# TopLevel.net
KiCad netlist of a schematic drawn in Altium Designer
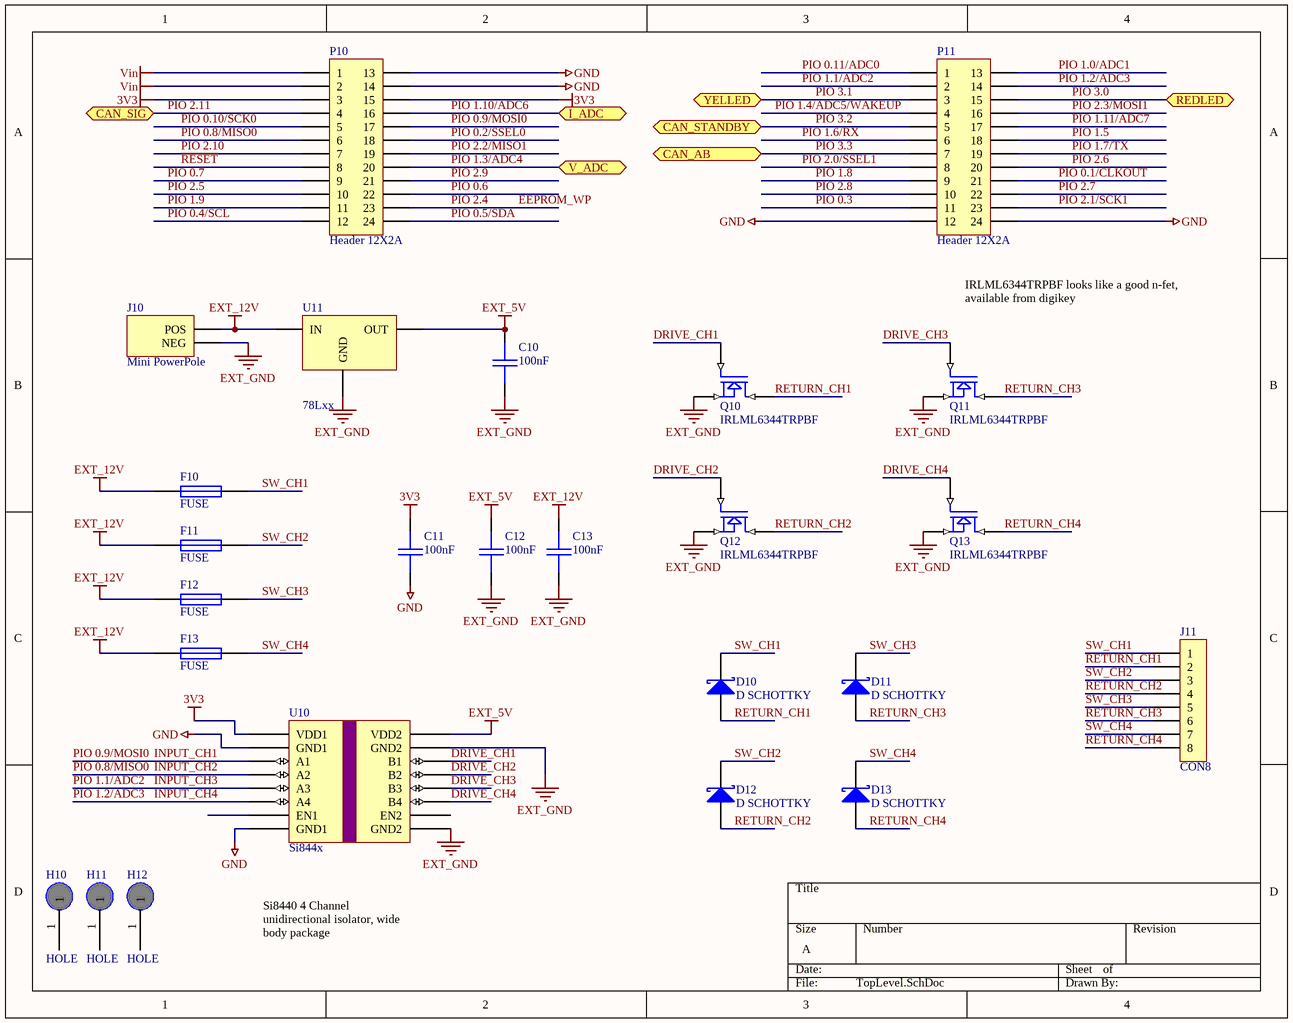
[diagram p0: TopLevel.SchDoc]

(export (version "E")
  (design (tool "Eeschema 10.0.6"))
  (components
    (comp (ref "C10")
      (value "100nF")
      (footprint "0603")
      (description "Capacitor")
      (libsource (lib "RCLDQ") (part "CAP"))
    )
    (comp (ref "C11")
      (value "100nF")
      (footprint "0603")
      (description "Capacitor")
      (libsource (lib "RCLDQ") (part "CAP"))
    )
    (comp (ref "C12")
      (value "100nF")
      (footprint "0603")
      (description "Capacitor")
      (libsource (lib "RCLDQ") (part "CAP"))
    )
    (comp (ref "C13")
      (value "100nF")
      (footprint "0603")
      (description "Capacitor")
      (libsource (lib "RCLDQ") (part "CAP"))
    )
    (comp (ref "D10")
      (value "D SCHOTTKY")
      (footprint "SMB")
      (description "Schottky Diode")
      (fields (field (name "MANUFACTURER") "Generic Components") (field (name "PUBLISHER") "Altium Limited"))
      (libsource (lib "RCLDQ") (part "D SCHOTTKY"))
    )
    (comp (ref "D11")
      (value "D SCHOTTKY")
      (footprint "SMB")
      (description "Schottky Diode")
      (fields (field (name "MANUFACTURER") "Generic Components") (field (name "PUBLISHER") "Altium Limited"))
      (libsource (lib "RCLDQ") (part "D SCHOTTKY"))
    )
    (comp (ref "D12")
      (value "D SCHOTTKY")
      (footprint "SMB")
      (description "Schottky Diode")
      (fields (field (name "MANUFACTURER") "Generic Components") (field (name "PUBLISHER") "Altium Limited"))
      (libsource (lib "RCLDQ") (part "D SCHOTTKY"))
    )
    (comp (ref "D13")
      (value "D SCHOTTKY")
      (footprint "SMB")
      (description "Schottky Diode")
      (fields (field (name "MANUFACTURER") "Generic Components") (field (name "PUBLISHER") "Altium Limited"))
      (libsource (lib "RCLDQ") (part "D SCHOTTKY"))
    )
    (comp (ref "F10")
      (value "FUSE")
      (footprint "LITTELFUSE-154")
      (description "Fuse")
      (libsource (lib "Miscellaneous") (part "FUSE"))
    )
    (comp (ref "F11")
      (value "FUSE")
      (footprint "LITTELFUSE-154")
      (description "Fuse")
      (libsource (lib "Miscellaneous") (part "FUSE"))
    )
    (comp (ref "F12")
      (value "FUSE")
      (footprint "LITTELFUSE-154")
      (description "Fuse")
      (libsource (lib "Miscellaneous") (part "FUSE"))
    )
    (comp (ref "F13")
      (value "FUSE")
      (footprint "LITTELFUSE-154")
      (description "Fuse")
      (libsource (lib "Miscellaneous") (part "FUSE"))
    )
    (comp (ref "H10")
      (value "HOLE")
      (footprint "M2.5")
      (description "Hole")
      (libsource (lib "Miscellaneous") (part "HOLE"))
    )
    (comp (ref "H11")
      (value "HOLE")
      (footprint "M2.5")
      (description "Hole")
      (libsource (lib "Miscellaneous") (part "HOLE"))
    )
    (comp (ref "H12")
      (value "HOLE")
      (footprint "M2.5")
      (description "Hole")
      (libsource (lib "Miscellaneous") (part "HOLE"))
    )
    (comp (ref "J10")
      (value "Mini PowerPole")
      (footprint "POWERPOLE25A-2")
      (libsource (lib "switchcard") (part "PowerPole"))
    )
    (comp (ref "J11")
      (value "CON8")
      (footprint "JST_SolderHoles")
      (description "8 Pin 3.5mm Screw Terminal  header")
      (libsource (lib "Connectors") (part "CON8"))
    )
    (comp (ref "P10")
      (value "Header 12X2A")
      (footprint "HDR2X12_CEN")
      (description "Header, 12-Pin, Dual row")
      (fields (field (name "PUBLISHER") "Altium Limited"))
      (libsource (lib "Miscellaneous Connectors") (part "Header 12X2A"))
    )
    (comp (ref "P11")
      (value "Header 12X2A")
      (footprint "HDR2X12_CEN")
      (description "Header, 12-Pin, Dual row")
      (fields (field (name "PUBLISHER") "Altium Limited"))
      (libsource (lib "Miscellaneous Connectors") (part "Header 12X2A"))
    )
    (comp (ref "Q10")
      (value "IRLML6344TRPBF")
      (footprint "SOT23-3")
      (description "5A, 30V N-Channel Enhancement mode FET")
      (libsource (lib "RCLDQ") (part "ZXM61N02F"))
    )
    (comp (ref "Q11")
      (value "IRLML6344TRPBF")
      (footprint "SOT23-3")
      (description "5A, 30V N-Channel Enhancement mode FET")
      (libsource (lib "RCLDQ") (part "ZXM61N02F"))
    )
    (comp (ref "Q12")
      (value "IRLML6344TRPBF")
      (footprint "SOT23-3")
      (description "5A, 30V N-Channel Enhancement mode FET")
      (libsource (lib "RCLDQ") (part "ZXM61N02F"))
    )
    (comp (ref "Q13")
      (value "IRLML6344TRPBF")
      (footprint "SOT23-3")
      (description "5A, 30V N-Channel Enhancement mode FET")
      (libsource (lib "RCLDQ") (part "ZXM61N02F"))
    )
    (comp (ref "U10")
      (value "Si844x")
      (footprint "SO16 (Wide)")
      (description "Si844x High Speed Digital Isolator")
      (libsource (lib "switchcard") (part "Si844x"))
    )
    (comp (ref "U11")
      (value "78Lxx")
      (footprint "78Lxx SO8")
      (libsource (lib "switchcard") (part "78Lxx SOIC LDO"))
    )
  )
  (nets
    (net (code "1") (name "/DRIVE_CH1") (class "Default")
      (node (ref "Q10") (pin "1") (pinfunction "G_1") (pintype "input"))
      (node (ref "U10") (pin "14") (pinfunction "B1_14") (pintype "bidirectional"))
    )
    (net (code "2") (name "/DRIVE_CH2") (class "Default")
      (node (ref "Q12") (pin "1") (pinfunction "G_1") (pintype "input"))
      (node (ref "U10") (pin "13") (pinfunction "B2_13") (pintype "bidirectional"))
    )
    (net (code "3") (name "/DRIVE_CH3") (class "Default")
      (node (ref "Q11") (pin "1") (pinfunction "G_1") (pintype "input"))
      (node (ref "U10") (pin "12") (pinfunction "B3_12") (pintype "bidirectional"))
    )
    (net (code "4") (name "/DRIVE_CH4") (class "Default")
      (node (ref "Q13") (pin "1") (pinfunction "G_1") (pintype "input"))
      (node (ref "U10") (pin "11") (pinfunction "B4_11") (pintype "bidirectional"))
    )
    (net (code "5") (name "/EEPROM_WP") (class "Default")
      (node (ref "P10") (pin "23") (pinfunction "23_23") (pintype "passive"))
    )
    (net (code "6") (name "/INPUT_CH1") (class "Default")
      (node (ref "P10") (pin "17") (pinfunction "17_17") (pintype "passive"))
      (node (ref "U10") (pin "3") (pinfunction "A1_3") (pintype "bidirectional"))
    )
    (net (code "7") (name "/INPUT_CH2") (class "Default")
      (node (ref "P10") (pin "6") (pinfunction "6_6") (pintype "passive"))
      (node (ref "U10") (pin "4") (pinfunction "A2_4") (pintype "bidirectional"))
    )
    (net (code "8") (name "/INPUT_CH3") (class "Default")
      (node (ref "P11") (pin "2") (pinfunction "2_2") (pintype "passive"))
      (node (ref "U10") (pin "5") (pinfunction "A3_5") (pintype "bidirectional"))
    )
    (net (code "9") (name "/INPUT_CH4") (class "Default")
      (node (ref "P11") (pin "14") (pinfunction "14_14") (pintype "passive"))
      (node (ref "U10") (pin "6") (pinfunction "A4_6") (pintype "bidirectional"))
    )
    (net (code "10") (name "/PIO 0.1{slash}CLKOUT") (class "Default")
      (node (ref "P11") (pin "21") (pinfunction "21_21") (pintype "passive"))
    )
    (net (code "11") (name "/PIO 0.2{slash}SSEL0") (class "Default")
      (node (ref "P10") (pin "18") (pinfunction "18_18") (pintype "passive"))
    )
    (net (code "12") (name "/PIO 0.3") (class "Default")
      (node (ref "P11") (pin "11") (pinfunction "11_11") (pintype "passive"))
    )
    (net (code "13") (name "/PIO 0.4{slash}SCL") (class "Default")
      (node (ref "P10") (pin "12") (pinfunction "12_12") (pintype "passive"))
    )
    (net (code "14") (name "/PIO 0.5{slash}SDA") (class "Default")
      (node (ref "P10") (pin "24") (pinfunction "24_24") (pintype "passive"))
    )
    (net (code "15") (name "/PIO 0.6") (class "Default")
      (node (ref "P10") (pin "22") (pinfunction "22_22") (pintype "passive"))
    )
    (net (code "16") (name "/PIO 0.7") (class "Default")
      (node (ref "P10") (pin "9") (pinfunction "9_9") (pintype "passive"))
    )
    (net (code "17") (name "/PIO 0.10{slash}SCK0") (class "Default")
      (node (ref "P10") (pin "5") (pinfunction "5_5") (pintype "passive"))
    )
    (net (code "18") (name "/PIO 0.11{slash}ADC0") (class "Default")
      (node (ref "P11") (pin "1") (pinfunction "1_1") (pintype "passive"))
    )
    (net (code "19") (name "/PIO 1.0{slash}ADC1") (class "Default")
      (node (ref "P11") (pin "13") (pinfunction "13_13") (pintype "passive"))
    )
    (net (code "20") (name "/PIO 1.3{slash}ADC4") (class "Default")
      (node (ref "P10") (pin "20") (pinfunction "20_20") (pintype "passive"))
    )
    (net (code "21") (name "/PIO 1.4{slash}ADC5{slash}WAKEUP") (class "Default")
      (node (ref "P11") (pin "4") (pinfunction "4_4") (pintype "passive"))
    )
    (net (code "22") (name "/PIO 1.5") (class "Default")
      (node (ref "P11") (pin "18") (pinfunction "18_18") (pintype "passive"))
    )
    (net (code "23") (name "/PIO 1.6{slash}RX") (class "Default")
      (node (ref "P11") (pin "6") (pinfunction "6_6") (pintype "passive"))
    )
    (net (code "24") (name "/PIO 1.7{slash}TX") (class "Default")
      (node (ref "P11") (pin "19") (pinfunction "19_19") (pintype "passive"))
    )
    (net (code "25") (name "/PIO 1.8") (class "Default")
      (node (ref "P11") (pin "9") (pinfunction "9_9") (pintype "passive"))
    )
    (net (code "26") (name "/PIO 1.9") (class "Default")
      (node (ref "P10") (pin "11") (pinfunction "11_11") (pintype "passive"))
    )
    (net (code "27") (name "/PIO 1.10{slash}ADC6") (class "Default")
      (node (ref "P10") (pin "16") (pinfunction "16_16") (pintype "passive"))
    )
    (net (code "28") (name "/PIO 1.11{slash}ADC7") (class "Default")
      (node (ref "P11") (pin "17") (pinfunction "17_17") (pintype "passive"))
    )
    (net (code "29") (name "/PIO 2.0{slash}SSEL1") (class "Default")
      (node (ref "P11") (pin "8") (pinfunction "8_8") (pintype "passive"))
    )
    (net (code "30") (name "/PIO 2.1{slash}SCK1") (class "Default")
      (node (ref "P11") (pin "23") (pinfunction "23_23") (pintype "passive"))
    )
    (net (code "31") (name "/PIO 2.2{slash}MISO1") (class "Default")
      (node (ref "P10") (pin "19") (pinfunction "19_19") (pintype "passive"))
    )
    (net (code "32") (name "/PIO 2.3{slash}MOSI1") (class "Default")
      (node (ref "P11") (pin "16") (pinfunction "16_16") (pintype "passive"))
    )
    (net (code "33") (name "/PIO 2.5") (class "Default")
      (node (ref "P10") (pin "10") (pinfunction "10_10") (pintype "passive"))
    )
    (net (code "34") (name "/PIO 2.6") (class "Default")
      (node (ref "P11") (pin "20") (pinfunction "20_20") (pintype "passive"))
    )
    (net (code "35") (name "/PIO 2.7") (class "Default")
      (node (ref "P11") (pin "22") (pinfunction "22_22") (pintype "passive"))
    )
    (net (code "36") (name "/PIO 2.8") (class "Default")
      (node (ref "P11") (pin "10") (pinfunction "10_10") (pintype "passive"))
    )
    (net (code "37") (name "/PIO 2.9") (class "Default")
      (node (ref "P10") (pin "21") (pinfunction "21_21") (pintype "passive"))
    )
    (net (code "38") (name "/PIO 2.10") (class "Default")
      (node (ref "P10") (pin "7") (pinfunction "7_7") (pintype "passive"))
    )
    (net (code "39") (name "/PIO 2.11") (class "Default")
      (node (ref "P10") (pin "4") (pinfunction "4_4") (pintype "passive"))
    )
    (net (code "40") (name "/PIO 3.0") (class "Default")
      (node (ref "P11") (pin "15") (pinfunction "15_15") (pintype "passive"))
    )
    (net (code "41") (name "/PIO 3.1") (class "Default")
      (node (ref "P11") (pin "3") (pinfunction "3_3") (pintype "passive"))
    )
    (net (code "42") (name "/PIO 3.2") (class "Default")
      (node (ref "P11") (pin "5") (pinfunction "5_5") (pintype "passive"))
    )
    (net (code "43") (name "/PIO 3.3") (class "Default")
      (node (ref "P11") (pin "7") (pinfunction "7_7") (pintype "passive"))
    )
    (net (code "44") (name "/RETURN_CH1") (class "Default")
      (node (ref "D10") (pin "A") (pinfunction "A_A") (pintype "passive"))
      (node (ref "J11") (pin "2") (pinfunction "2_2") (pintype "passive"))
      (node (ref "Q10") (pin "3") (pinfunction "D_3") (pintype "input"))
    )
    (net (code "45") (name "/RETURN_CH2") (class "Default")
      (node (ref "D12") (pin "A") (pinfunction "A_A") (pintype "passive"))
      (node (ref "J11") (pin "4") (pinfunction "4_4") (pintype "passive"))
      (node (ref "Q12") (pin "3") (pinfunction "D_3") (pintype "input"))
    )
    (net (code "46") (name "/RETURN_CH3") (class "Default")
      (node (ref "D11") (pin "A") (pinfunction "A_A") (pintype "passive"))
      (node (ref "J11") (pin "6") (pinfunction "6_6") (pintype "passive"))
      (node (ref "Q11") (pin "3") (pinfunction "D_3") (pintype "input"))
    )
    (net (code "47") (name "/RETURN_CH4") (class "Default")
      (node (ref "D13") (pin "A") (pinfunction "A_A") (pintype "passive"))
      (node (ref "J11") (pin "8") (pinfunction "8_8") (pintype "passive"))
      (node (ref "Q13") (pin "3") (pinfunction "D_3") (pintype "input"))
    )
    (net (code "48") (name "/SW_CH1") (class "Default")
      (node (ref "D10") (pin "K") (pinfunction "K_K") (pintype "passive"))
      (node (ref "F10") (pin "2") (pinfunction "2_2") (pintype "passive"))
      (node (ref "J11") (pin "1") (pinfunction "1_1") (pintype "passive"))
    )
    (net (code "49") (name "/SW_CH2") (class "Default")
      (node (ref "D12") (pin "K") (pinfunction "K_K") (pintype "passive"))
      (node (ref "F11") (pin "2") (pinfunction "2_2") (pintype "passive"))
      (node (ref "J11") (pin "3") (pinfunction "3_3") (pintype "passive"))
    )
    (net (code "50") (name "/SW_CH3") (class "Default")
      (node (ref "D11") (pin "K") (pinfunction "K_K") (pintype "passive"))
      (node (ref "F12") (pin "2") (pinfunction "2_2") (pintype "passive"))
      (node (ref "J11") (pin "5") (pinfunction "5_5") (pintype "passive"))
    )
    (net (code "51") (name "/SW_CH4") (class "Default")
      (node (ref "D13") (pin "K") (pinfunction "K_K") (pintype "passive"))
      (node (ref "F13") (pin "2") (pinfunction "2_2") (pintype "passive"))
      (node (ref "J11") (pin "7") (pinfunction "7_7") (pintype "passive"))
    )
    (net (code "52") (name "/~{RESET}") (class "Default")
      (node (ref "P10") (pin "8") (pinfunction "8_8") (pintype "passive"))
    )
    (net (code "53") (name "3V3") (class "Default")
      (node (ref "C11") (pin "1") (pinfunction "1_1") (pintype "passive"))
      (node (ref "P10") (pin "15") (pinfunction "15_15") (pintype "passive"))
      (node (ref "P10") (pin "3") (pinfunction "3_3") (pintype "passive"))
      (node (ref "U10") (pin "1") (pinfunction "VDD1_1") (pintype "passive"))
    )
    (net (code "54") (name "EXT_5V") (class "Default")
      (node (ref "C10") (pin "1") (pinfunction "1_1") (pintype "passive"))
      (node (ref "C12") (pin "1") (pinfunction "1_1") (pintype "passive"))
      (node (ref "U10") (pin "16") (pinfunction "VDD2_16") (pintype "passive"))
      (node (ref "U11") (pin "OUTPUT") (pinfunction "OUT_OUTPUT") (pintype "power_in"))
    )
    (net (code "55") (name "EXT_12V") (class "Default")
      (node (ref "C13") (pin "1") (pinfunction "1_1") (pintype "passive"))
      (node (ref "F10") (pin "1") (pinfunction "1_1") (pintype "passive"))
      (node (ref "F11") (pin "1") (pinfunction "1_1") (pintype "passive"))
      (node (ref "F12") (pin "1") (pinfunction "1_1") (pintype "passive"))
      (node (ref "F13") (pin "1") (pinfunction "1_1") (pintype "passive"))
      (node (ref "J10") (pin "POS") (pinfunction "POS_POS") (pintype "power_in"))
      (node (ref "U11") (pin "INPUT") (pinfunction "IN_INPUT") (pintype "power_in"))
    )
    (net (code "56") (name "EXT_GND") (class "Default")
      (node (ref "C10") (pin "2") (pinfunction "2_2") (pintype "passive"))
      (node (ref "C12") (pin "2") (pinfunction "2_2") (pintype "passive"))
      (node (ref "C13") (pin "2") (pinfunction "2_2") (pintype "passive"))
      (node (ref "J10") (pin "NEG") (pinfunction "NEG_NEG") (pintype "power_in"))
      (node (ref "Q10") (pin "2") (pinfunction "S_2") (pintype "input"))
      (node (ref "Q11") (pin "2") (pinfunction "S_2") (pintype "input"))
      (node (ref "Q12") (pin "2") (pinfunction "S_2") (pintype "input"))
      (node (ref "Q13") (pin "2") (pinfunction "S_2") (pintype "input"))
      (node (ref "U10") (pin "15") (pinfunction "GND2_15") (pintype "passive"))
      (node (ref "U10") (pin "9") (pinfunction "GND2_9") (pintype "passive"))
      (node (ref "U11") (pin "COMMON") (pinfunction "GND_COMMON") (pintype "power_in"))
    )
    (net (code "57") (name "GND") (class "Default")
      (node (ref "C11") (pin "2") (pinfunction "2_2") (pintype "passive"))
      (node (ref "P10") (pin "13") (pinfunction "13_13") (pintype "passive"))
      (node (ref "P10") (pin "14") (pinfunction "14_14") (pintype "passive"))
      (node (ref "P11") (pin "12") (pinfunction "12_12") (pintype "passive"))
      (node (ref "P11") (pin "24") (pinfunction "24_24") (pintype "passive"))
      (node (ref "U10") (pin "2") (pinfunction "GND1_2") (pintype "passive"))
      (node (ref "U10") (pin "8") (pinfunction "GND1_8") (pintype "passive"))
    )
    (net (code "58") (name "Vin") (class "Default")
      (node (ref "P10") (pin "1") (pinfunction "1_1") (pintype "passive"))
      (node (ref "P10") (pin "2") (pinfunction "2_2") (pintype "passive"))
    )
    (net (code "59") (name "unconnected-(H10-Pad1)") (class "Default")
      (node (ref "H10") (pin "1") (pinfunction "1_1") (pintype "passive"))
    )
    (net (code "60") (name "unconnected-(H11-Pad1)") (class "Default")
      (node (ref "H11") (pin "1") (pinfunction "1_1") (pintype "passive"))
    )
    (net (code "61") (name "unconnected-(H12-Pad1)") (class "Default")
      (node (ref "H12") (pin "1") (pinfunction "1_1") (pintype "passive"))
    )
    (net (code "62") (name "unconnected-(U10-EN1-Pad7)") (class "Default")
      (node (ref "U10") (pin "7") (pinfunction "EN1_7") (pintype "passive"))
    )
    (net (code "63") (name "unconnected-(U10-EN2-Pad10)") (class "Default")
      (node (ref "U10") (pin "10") (pinfunction "EN2_10") (pintype "passive"))
    )
  )
)
